# Ext_PTT_and_Indication.net
KiCad netlist of a schematic drawn in Altium Designer
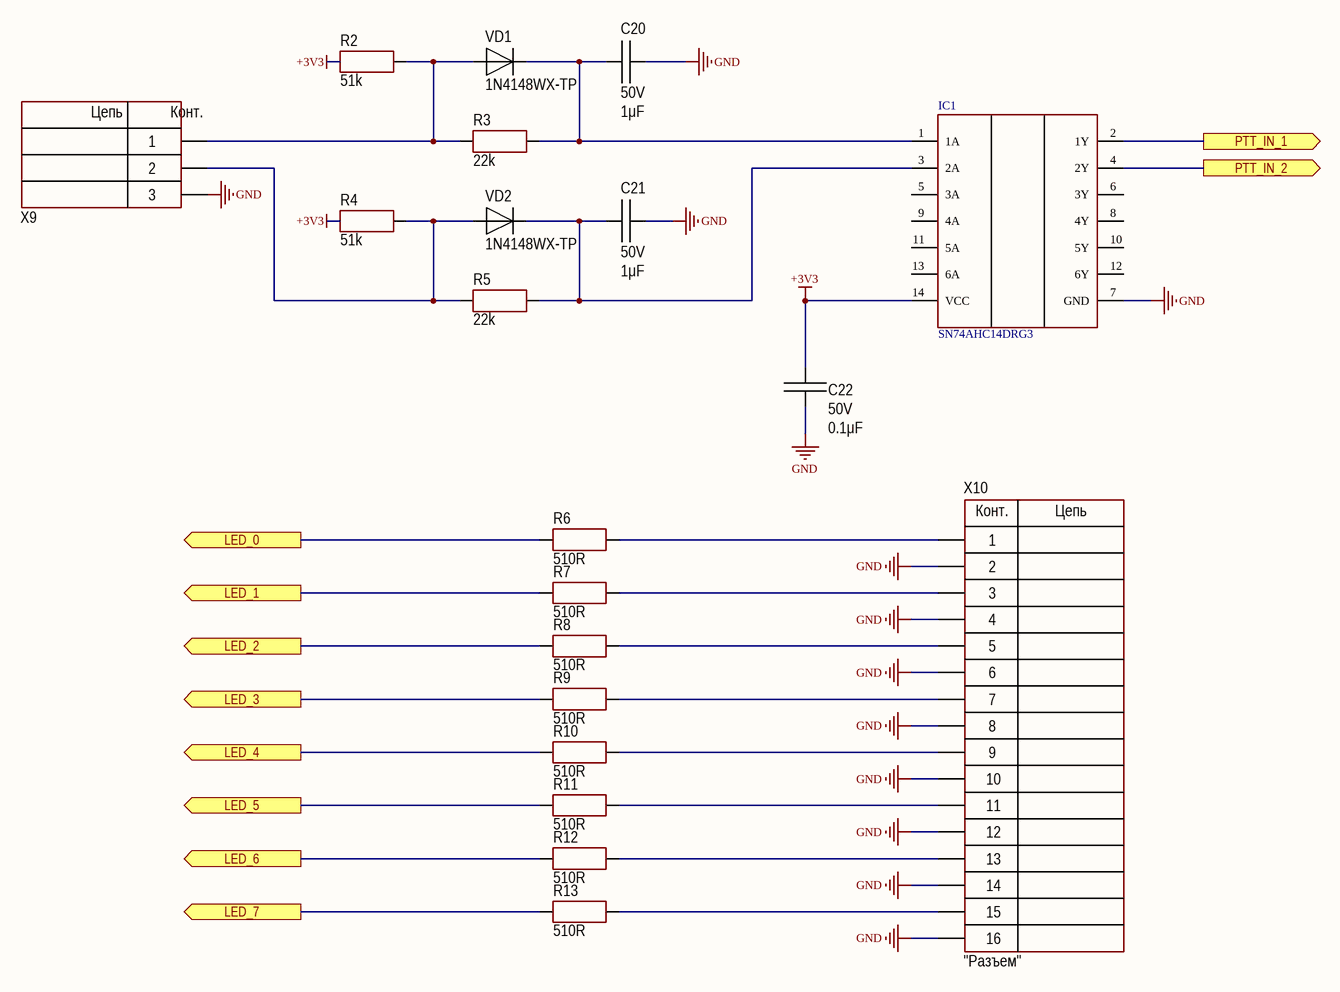
[diagram p0: Ext_PTT_and_Indication.SchDoc]

(export (version "E")
  (design (tool "Eeschema 10.0.6"))
  (components
    (comp (ref "C20")
      (value "1μF")
      (footprint "standard-case:CAP: 1206")
      (fields
        (field (name "MANUFACTURER") "Yageo")
        (field (name "PARTNUMBER") "CC1206KRX7R9BB104")
        (field (name "VALUEMANUFACTURERPARTNUMBER") "Ceramic capacitor, 1μF, X7R, ±10%, 50V, 1206, -55...+125°C")
        (field (name "VOLTAGE") "50V")
      )
      (libsource (lib "capacitor") (part "Ceramic_1206"))
    )
    (comp (ref "C21")
      (value "1μF")
      (footprint "standard-case:CAP: 1206")
      (fields
        (field (name "MANUFACTURER") "Yageo")
        (field (name "PARTNUMBER") "CC1206KRX7R9BB104")
        (field (name "VALUEMANUFACTURERPARTNUMBER") "Ceramic capacitor, 1μF, X7R, ±10%, 50V, 1206, -55...+125°C")
        (field (name "VOLTAGE") "50V")
      )
      (libsource (lib "capacitor") (part "Ceramic_1206"))
    )
    (comp (ref "C22")
      (value "0.1μF")
      (footprint "standard-case:CAP: 1206")
      (fields
        (field (name "MANUFACTURER") "Yageo")
        (field (name "PARTNUMBER") "CC1206KRX7R9BB104")
        (field (name "VALUEMANUFACTURERPARTNUMBER") "Ceramic capacitor, 0.1μF, X7R, ±10%, 50V, 1206, -55...+125°C")
        (field (name "VOLTAGE") "50V")
      )
      (libsource (lib "capacitor") (part "Ceramic_1206"))
    )
    (comp (ref "IC1")
      (value "SN74AHC14DRG3")
      (footprint "D0014A_N")
      (description "Integrated Circuit")
      (fields (field (name "MANUFACTURER_PART_NUMBER") "74HC14N,652"))
      (libsource (lib "74AHC14D") (part "SN74AHC14DRG3"))
    )
    (comp (ref "R2")
      (value "51k")
      (footprint "RES: 1206")
      (fields
        (field (name "MANUFACTURER") "Yageo")
        (field (name "PARTNUMBER") "RC1206JR-07100RL")
        (field (name "VALUEMANUFACTURERPARTNUMBER") "Resistor film, 51k, , 1206, 0.25W, -55...+125°C")
      )
      (libsource (lib "") (part "Resistor_1206_1"))
    )
    (comp (ref "R3")
      (value "22k")
      (footprint "RES: 1206")
      (fields
        (field (name "MANUFACTURER") "Yageo")
        (field (name "PARTNUMBER") "RC1206JR-07100RL")
        (field (name "VALUEMANUFACTURERPARTNUMBER") "Resistor film, 22k, , 1206, 0.25W, -55...+125°C")
      )
      (libsource (lib "") (part "Resistor_1206_1"))
    )
    (comp (ref "R4")
      (value "51k")
      (footprint "RES: 1206")
      (fields
        (field (name "MANUFACTURER") "Yageo")
        (field (name "PARTNUMBER") "RC1206JR-07100RL")
        (field (name "VALUEMANUFACTURERPARTNUMBER") "Resistor film, 51k, , 1206, 0.25W, -55...+125°C")
      )
      (libsource (lib "") (part "Resistor_1206_1"))
    )
    (comp (ref "R5")
      (value "22k")
      (footprint "RES: 1206")
      (fields
        (field (name "MANUFACTURER") "Yageo")
        (field (name "PARTNUMBER") "RC1206JR-07100RL")
        (field (name "VALUEMANUFACTURERPARTNUMBER") "Resistor film, 22k, , 1206, 0.25W, -55...+125°C")
      )
      (libsource (lib "") (part "Resistor_1206_1"))
    )
    (comp (ref "R6")
      (value "510R")
      (footprint "RES: 1206")
      (fields
        (field (name "MANUFACTURER") "Yageo")
        (field (name "PARTNUMBER") "RC1206JR-07100RL")
        (field (name "VALUEMANUFACTURERPARTNUMBER") "Resistor film, 510R, , 1206, 0.25W, -55...+125°C")
      )
      (libsource (lib "R1206") (part "Resistor_1206"))
    )
    (comp (ref "R7")
      (value "510R")
      (footprint "RES: 1206")
      (fields
        (field (name "MANUFACTURER") "Yageo")
        (field (name "PARTNUMBER") "RC1206JR-07100RL")
        (field (name "VALUEMANUFACTURERPARTNUMBER") "Resistor film, 510R, , 1206, 0.25W, -55...+125°C")
      )
      (libsource (lib "R1206") (part "Resistor_1206"))
    )
    (comp (ref "R8")
      (value "510R")
      (footprint "RES: 1206")
      (fields
        (field (name "MANUFACTURER") "Yageo")
        (field (name "PARTNUMBER") "RC1206JR-07100RL")
        (field (name "VALUEMANUFACTURERPARTNUMBER") "Resistor film, 510R, , 1206, 0.25W, -55...+125°C")
      )
      (libsource (lib "R1206") (part "Resistor_1206"))
    )
    (comp (ref "R9")
      (value "510R")
      (footprint "RES: 1206")
      (fields
        (field (name "MANUFACTURER") "Yageo")
        (field (name "PARTNUMBER") "RC1206JR-07100RL")
        (field (name "VALUEMANUFACTURERPARTNUMBER") "Resistor film, 510R, , 1206, 0.25W, -55...+125°C")
      )
      (libsource (lib "R1206") (part "Resistor_1206"))
    )
    (comp (ref "R10")
      (value "510R")
      (footprint "RES: 1206")
      (fields
        (field (name "MANUFACTURER") "Yageo")
        (field (name "PARTNUMBER") "RC1206JR-07100RL")
        (field (name "VALUEMANUFACTURERPARTNUMBER") "Resistor film, 510R, , 1206, 0.25W, -55...+125°C")
      )
      (libsource (lib "R1206") (part "Resistor_1206"))
    )
    (comp (ref "R11")
      (value "510R")
      (footprint "RES: 1206")
      (fields
        (field (name "MANUFACTURER") "Yageo")
        (field (name "PARTNUMBER") "RC1206JR-07100RL")
        (field (name "VALUEMANUFACTURERPARTNUMBER") "Resistor film, 510R, , 1206, 0.25W, -55...+125°C")
      )
      (libsource (lib "R1206") (part "Resistor_1206"))
    )
    (comp (ref "R12")
      (value "510R")
      (footprint "RES: 1206")
      (fields
        (field (name "MANUFACTURER") "Yageo")
        (field (name "PARTNUMBER") "RC1206JR-07100RL")
        (field (name "VALUEMANUFACTURERPARTNUMBER") "Resistor film, 510R, , 1206, 0.25W, -55...+125°C")
      )
      (libsource (lib "R1206") (part "Resistor_1206"))
    )
    (comp (ref "R13")
      (value "510R")
      (footprint "RES: 1206")
      (fields
        (field (name "MANUFACTURER") "Yageo")
        (field (name "PARTNUMBER") "RC1206JR-07100RL")
        (field (name "VALUEMANUFACTURERPARTNUMBER") "Resistor film, 510R, , 1206, 0.25W, -55...+125°C")
      )
      (libsource (lib "R1206") (part "Resistor_1206"))
    )
    (comp (ref "VD1")
      (value "~")
      (footprint "standard-case:DIODE: SOD123")
      (fields
        (field (name "MANUFACTURER") "Micro Commercial")
        (field (name "VALUEMANUFACTURERPARTNUMBER") "Single diode, 75V, 150mA, 1V, 4ns, SOD-323, -55...+150°C")
        (field (name "VOLTAGE") "75V")
        (field (name "PARTNUMBER") "1N4148WX-TP")
      )
      (libsource (lib "diode") (part "Diode_single"))
    )
    (comp (ref "VD2")
      (value "~")
      (footprint "standard-case:DIODE: SOD123")
      (fields
        (field (name "MANUFACTURER") "Micro Commercial")
        (field (name "VALUEMANUFACTURERPARTNUMBER") "Single diode, 75V, 150mA, 1V, 4ns, SOD-323, -55...+150°C")
        (field (name "VOLTAGE") "75V")
        (field (name "PARTNUMBER") "1N4148WX-TP")
      )
      (libsource (lib "diode") (part "Diode_single"))
    )
    (comp (ref "X9")
      (value "~")
      (footprint "2EDGR-5.08-03P")
      (fields
        (field (name "MANUFACTURER") "Connfly")
        (field (name "VALUEMANUFACTURERPARTNUMBER") "Connector, 6pin, 2.54mm, 500VAC, 3A")
        (field (name "PARTNUMBER") "PBS-6")
      )
      (libsource (lib "K3NG_SCH_Libs") (part "2EDGR-5.08-03P"))
    )
    (comp (ref "X10")
      (value "~")
      (footprint "custom-case:CON: IDC-16MS")
      (fields
        (field (name "MANUFACTURER") "Connfly")
        (field (name "VALUEMANUFACTURERPARTNUMBER") "Connector, 16pin, 2.54mm, 250VAC, 3A")
        (field (name "PARTNUMBER") "IDC-16")
        (field (name "COMMENTTEXT") "\"Разъем\"")
      )
      (libsource (lib "connector") (part "IDC-16"))
    )
  )
  (nets
    (net (code "1") (name "+3V3") (class "Default")
      (node (ref "C22") (pin "2") (pinfunction "2_2") (pintype "passive"))
      (node (ref "IC1") (pin "14") (pinfunction "VCC_14") (pintype "passive"))
      (node (ref "R2") (pin "2") (pinfunction "2_2") (pintype "passive"))
      (node (ref "R4") (pin "2") (pinfunction "2_2") (pintype "passive"))
    )
    (net (code "2") (name "/LED_0") (class "Default")
      (node (ref "R6") (pin "1") (pinfunction "1_1") (pintype "passive"))
    )
    (net (code "3") (name "/LED_1") (class "Default")
      (node (ref "R7") (pin "1") (pinfunction "1_1") (pintype "passive"))
    )
    (net (code "4") (name "/LED_2") (class "Default")
      (node (ref "R8") (pin "1") (pinfunction "1_1") (pintype "passive"))
    )
    (net (code "5") (name "/LED_3") (class "Default")
      (node (ref "R9") (pin "1") (pinfunction "1_1") (pintype "passive"))
    )
    (net (code "6") (name "/LED_4") (class "Default")
      (node (ref "R10") (pin "1") (pinfunction "1_1") (pintype "passive"))
    )
    (net (code "7") (name "/LED_5") (class "Default")
      (node (ref "R11") (pin "1") (pinfunction "1_1") (pintype "passive"))
    )
    (net (code "8") (name "/LED_6") (class "Default")
      (node (ref "R12") (pin "1") (pinfunction "1_1") (pintype "passive"))
    )
    (net (code "9") (name "/LED_7") (class "Default")
      (node (ref "R13") (pin "1") (pinfunction "1_1") (pintype "passive"))
    )
    (net (code "10") (name "/PTT_IN_1") (class "Default")
      (node (ref "IC1") (pin "2") (pinfunction "1Y_2") (pintype "passive"))
    )
    (net (code "11") (name "/PTT_IN_2") (class "Default")
      (node (ref "IC1") (pin "4") (pinfunction "2Y_4") (pintype "passive"))
    )
    (net (code "12") (name "GND") (class "Default")
      (node (ref "C20") (pin "1") (pinfunction "1_1") (pintype "passive"))
      (node (ref "C21") (pin "1") (pinfunction "1_1") (pintype "passive"))
      (node (ref "C22") (pin "1") (pinfunction "1_1") (pintype "passive"))
      (node (ref "IC1") (pin "7") (pinfunction "GND_7") (pintype "passive"))
      (node (ref "X10") (pin "10") (pinfunction "10_10") (pintype "power_in"))
      (node (ref "X10") (pin "12") (pinfunction "12_12") (pintype "power_in"))
      (node (ref "X10") (pin "14") (pinfunction "14_14") (pintype "power_in"))
      (node (ref "X10") (pin "16") (pinfunction "16_16") (pintype "power_in"))
      (node (ref "X10") (pin "2") (pinfunction "2_2") (pintype "passive"))
      (node (ref "X10") (pin "4") (pinfunction "4_4") (pintype "power_in"))
      (node (ref "X10") (pin "6") (pinfunction "6_6") (pintype "power_in"))
      (node (ref "X10") (pin "8") (pinfunction "8_8") (pintype "power_in"))
      (node (ref "X9") (pin "3") (pinfunction "3_3") (pintype "power_in"))
    )
    (net (code "13") (name "Net-(IC1-1A)") (class "Default")
      (node (ref "C20") (pin "2") (pinfunction "2_2") (pintype "passive"))
      (node (ref "IC1") (pin "1") (pinfunction "1A_1") (pintype "passive"))
      (node (ref "R3") (pin "1") (pinfunction "1_1") (pintype "passive"))
      (node (ref "VD1") (pin "2") (pinfunction "2_2") (pintype "passive"))
    )
    (net (code "14") (name "Net-(IC1-2A)") (class "Default")
      (node (ref "C21") (pin "2") (pinfunction "2_2") (pintype "passive"))
      (node (ref "IC1") (pin "3") (pinfunction "2A_3") (pintype "passive"))
      (node (ref "R5") (pin "1") (pinfunction "1_1") (pintype "passive"))
      (node (ref "VD2") (pin "2") (pinfunction "2_2") (pintype "passive"))
    )
    (net (code "15") (name "Net-(R2-Pad1)") (class "Default")
      (node (ref "R2") (pin "1") (pinfunction "1_1") (pintype "passive"))
      (node (ref "R3") (pin "2") (pinfunction "2_2") (pintype "passive"))
      (node (ref "VD1") (pin "1") (pinfunction "1_1") (pintype "passive"))
      (node (ref "X9") (pin "1") (pinfunction "1_1") (pintype "passive"))
    )
    (net (code "16") (name "Net-(R4-Pad1)") (class "Default")
      (node (ref "R4") (pin "1") (pinfunction "1_1") (pintype "passive"))
      (node (ref "R5") (pin "2") (pinfunction "2_2") (pintype "passive"))
      (node (ref "VD2") (pin "1") (pinfunction "1_1") (pintype "passive"))
      (node (ref "X9") (pin "2") (pinfunction "2_2") (pintype "passive"))
    )
    (net (code "17") (name "Net-(R6-Pad2)") (class "Default")
      (node (ref "R6") (pin "2") (pinfunction "2_2") (pintype "passive"))
      (node (ref "X10") (pin "1") (pinfunction "1_1") (pintype "passive"))
    )
    (net (code "18") (name "Net-(R7-Pad2)") (class "Default")
      (node (ref "R7") (pin "2") (pinfunction "2_2") (pintype "passive"))
      (node (ref "X10") (pin "3") (pinfunction "3_3") (pintype "power_in"))
    )
    (net (code "19") (name "Net-(R8-Pad2)") (class "Default")
      (node (ref "R8") (pin "2") (pinfunction "2_2") (pintype "passive"))
      (node (ref "X10") (pin "5") (pinfunction "5_5") (pintype "power_in"))
    )
    (net (code "20") (name "Net-(R9-Pad2)") (class "Default")
      (node (ref "R9") (pin "2") (pinfunction "2_2") (pintype "passive"))
      (node (ref "X10") (pin "7") (pinfunction "7_7") (pintype "power_in"))
    )
    (net (code "21") (name "Net-(R10-Pad2)") (class "Default")
      (node (ref "R10") (pin "2") (pinfunction "2_2") (pintype "passive"))
      (node (ref "X10") (pin "9") (pinfunction "9_9") (pintype "power_in"))
    )
    (net (code "22") (name "Net-(R11-Pad2)") (class "Default")
      (node (ref "R11") (pin "2") (pinfunction "2_2") (pintype "passive"))
      (node (ref "X10") (pin "11") (pinfunction "11_11") (pintype "power_in"))
    )
    (net (code "23") (name "Net-(R12-Pad2)") (class "Default")
      (node (ref "R12") (pin "2") (pinfunction "2_2") (pintype "passive"))
      (node (ref "X10") (pin "13") (pinfunction "13_13") (pintype "power_in"))
    )
    (net (code "24") (name "Net-(R13-Pad2)") (class "Default")
      (node (ref "R13") (pin "2") (pinfunction "2_2") (pintype "passive"))
      (node (ref "X10") (pin "15") (pinfunction "15_15") (pintype "power_in"))
    )
    (net (code "25") (name "unconnected-(IC1-3A-Pad5)") (class "Default")
      (node (ref "IC1") (pin "5") (pinfunction "3A_5") (pintype "passive"))
    )
    (net (code "26") (name "unconnected-(IC1-3Y-Pad6)") (class "Default")
      (node (ref "IC1") (pin "6") (pinfunction "3Y_6") (pintype "passive"))
    )
    (net (code "27") (name "unconnected-(IC1-4A-Pad9)") (class "Default")
      (node (ref "IC1") (pin "9") (pinfunction "4A_9") (pintype "passive"))
    )
    (net (code "28") (name "unconnected-(IC1-4Y-Pad8)") (class "Default")
      (node (ref "IC1") (pin "8") (pinfunction "4Y_8") (pintype "passive"))
    )
    (net (code "29") (name "unconnected-(IC1-5A-Pad11)") (class "Default")
      (node (ref "IC1") (pin "11") (pinfunction "5A_11") (pintype "passive"))
    )
    (net (code "30") (name "unconnected-(IC1-5Y-Pad10)") (class "Default")
      (node (ref "IC1") (pin "10") (pinfunction "5Y_10") (pintype "passive"))
    )
    (net (code "31") (name "unconnected-(IC1-6A-Pad13)") (class "Default")
      (node (ref "IC1") (pin "13") (pinfunction "6A_13") (pintype "passive"))
    )
    (net (code "32") (name "unconnected-(IC1-6Y-Pad12)") (class "Default")
      (node (ref "IC1") (pin "12") (pinfunction "6Y_12") (pintype "passive"))
    )
  )
)
